# Parallel_Interfaces.net
KiCad netlist of a schematic drawn in Altium Designer
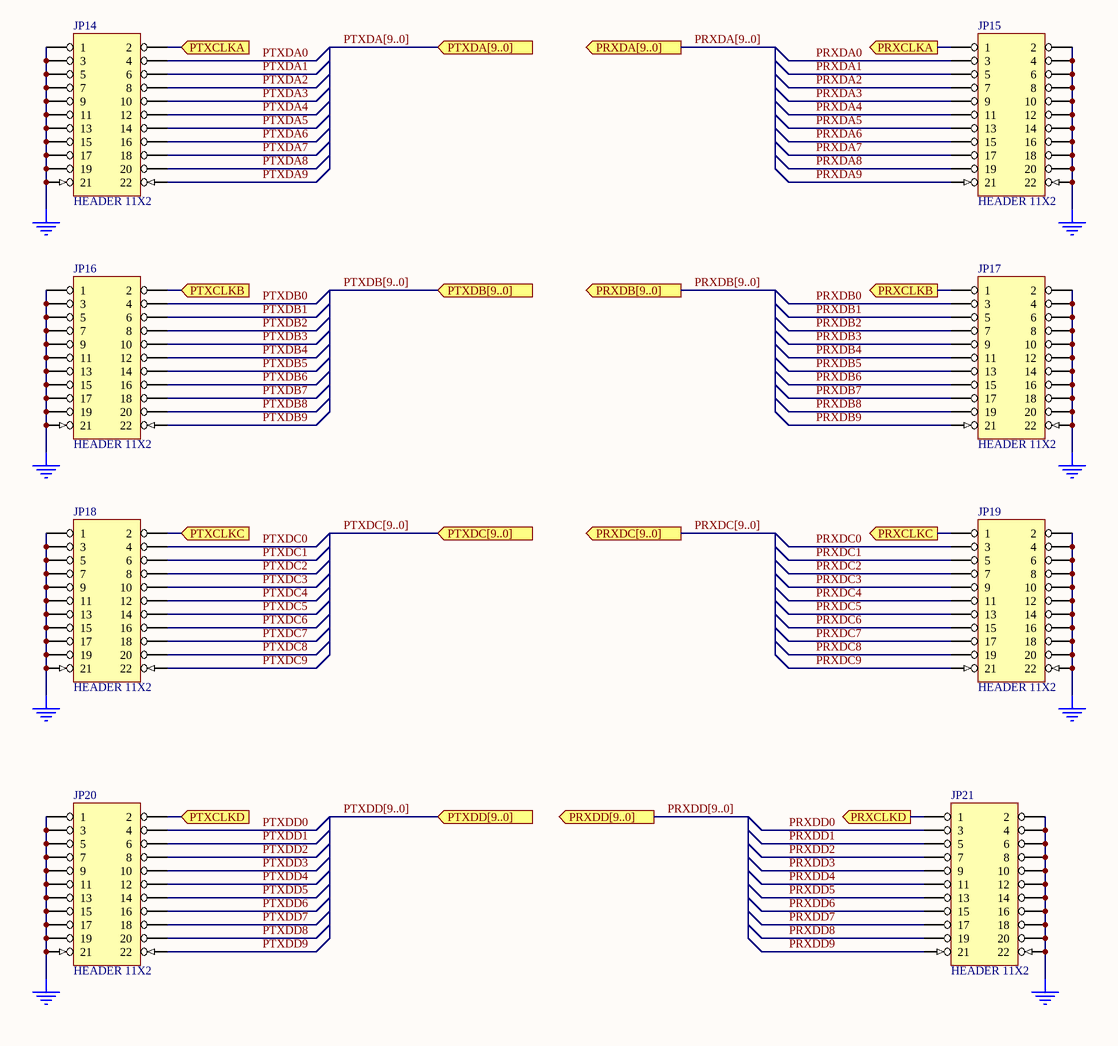
[diagram p0: Parallel Interfaces.SchDoc]

(export (version "E")
  (design (tool "Eeschema 10.0.6"))
  (components
    (comp (ref "JP14")
      (value "~")
      (footprint "2X11PIN")
      (libsource (lib "Cypress Molson") (part "HEADER 11X2"))
    )
    (comp (ref "JP15")
      (value "~")
      (footprint "2X11PIN")
      (libsource (lib "Cypress Molson") (part "HEADER 11X2"))
    )
    (comp (ref "JP16")
      (value "~")
      (footprint "2X11PIN")
      (libsource (lib "Cypress Molson") (part "HEADER 11X2"))
    )
    (comp (ref "JP17")
      (value "~")
      (footprint "2X11PIN")
      (libsource (lib "Cypress Molson") (part "HEADER 11X2"))
    )
    (comp (ref "JP18")
      (value "~")
      (footprint "2X11PIN")
      (libsource (lib "Cypress Molson") (part "HEADER 11X2"))
    )
    (comp (ref "JP19")
      (value "~")
      (footprint "2X11PIN")
      (libsource (lib "Cypress Molson") (part "HEADER 11X2"))
    )
    (comp (ref "JP20")
      (value "~")
      (footprint "2X11PIN")
      (libsource (lib "Cypress Molson") (part "HEADER 11X2"))
    )
    (comp (ref "JP21")
      (value "~")
      (footprint "2X11PIN")
      (libsource (lib "Cypress Molson") (part "HEADER 11X2"))
    )
  )
  (nets
    (net (code "1") (name "/PRXCLKA") (class "Default")
      (node (ref "JP15") (pin "1") (pinfunction "1_1") (pintype "passive"))
    )
    (net (code "2") (name "/PRXCLKB") (class "Default")
      (node (ref "JP17") (pin "1") (pinfunction "1_1") (pintype "passive"))
    )
    (net (code "3") (name "/PRXCLKC") (class "Default")
      (node (ref "JP19") (pin "1") (pinfunction "1_1") (pintype "passive"))
    )
    (net (code "4") (name "/PRXCLKD") (class "Default")
      (node (ref "JP21") (pin "1") (pinfunction "1_1") (pintype "passive"))
    )
    (net (code "5") (name "/PRXDA0") (class "Default")
      (node (ref "JP15") (pin "3") (pinfunction "3_3") (pintype "passive"))
    )
    (net (code "6") (name "/PRXDA1") (class "Default")
      (node (ref "JP15") (pin "5") (pinfunction "5_5") (pintype "passive"))
    )
    (net (code "7") (name "/PRXDA2") (class "Default")
      (node (ref "JP15") (pin "7") (pinfunction "7_7") (pintype "passive"))
    )
    (net (code "8") (name "/PRXDA3") (class "Default")
      (node (ref "JP15") (pin "9") (pinfunction "9_9") (pintype "passive"))
    )
    (net (code "9") (name "/PRXDA4") (class "Default")
      (node (ref "JP15") (pin "11") (pinfunction "11_11") (pintype "passive"))
    )
    (net (code "10") (name "/PRXDA5") (class "Default")
      (node (ref "JP15") (pin "13") (pinfunction "13_13") (pintype "passive"))
    )
    (net (code "11") (name "/PRXDA6") (class "Default")
      (node (ref "JP15") (pin "15") (pinfunction "15_15") (pintype "passive"))
    )
    (net (code "12") (name "/PRXDA7") (class "Default")
      (node (ref "JP15") (pin "17") (pinfunction "17_17") (pintype "passive"))
    )
    (net (code "13") (name "/PRXDA8") (class "Default")
      (node (ref "JP15") (pin "19") (pinfunction "19_19") (pintype "passive"))
    )
    (net (code "14") (name "/PRXDA9") (class "Default")
      (node (ref "JP15") (pin "21") (pinfunction "21_21") (pintype "input"))
    )
    (net (code "16") (name "/PRXDB0") (class "Default")
      (node (ref "JP17") (pin "3") (pinfunction "3_3") (pintype "passive"))
    )
    (net (code "17") (name "/PRXDB1") (class "Default")
      (node (ref "JP17") (pin "5") (pinfunction "5_5") (pintype "passive"))
    )
    (net (code "18") (name "/PRXDB2") (class "Default")
      (node (ref "JP17") (pin "7") (pinfunction "7_7") (pintype "passive"))
    )
    (net (code "19") (name "/PRXDB3") (class "Default")
      (node (ref "JP17") (pin "9") (pinfunction "9_9") (pintype "passive"))
    )
    (net (code "20") (name "/PRXDB4") (class "Default")
      (node (ref "JP17") (pin "11") (pinfunction "11_11") (pintype "passive"))
    )
    (net (code "21") (name "/PRXDB5") (class "Default")
      (node (ref "JP17") (pin "13") (pinfunction "13_13") (pintype "passive"))
    )
    (net (code "22") (name "/PRXDB6") (class "Default")
      (node (ref "JP17") (pin "15") (pinfunction "15_15") (pintype "passive"))
    )
    (net (code "23") (name "/PRXDB7") (class "Default")
      (node (ref "JP17") (pin "17") (pinfunction "17_17") (pintype "passive"))
    )
    (net (code "24") (name "/PRXDB8") (class "Default")
      (node (ref "JP17") (pin "19") (pinfunction "19_19") (pintype "passive"))
    )
    (net (code "25") (name "/PRXDB9") (class "Default")
      (node (ref "JP17") (pin "21") (pinfunction "21_21") (pintype "input"))
    )
    (net (code "27") (name "/PRXDC0") (class "Default")
      (node (ref "JP19") (pin "3") (pinfunction "3_3") (pintype "passive"))
    )
    (net (code "28") (name "/PRXDC1") (class "Default")
      (node (ref "JP19") (pin "5") (pinfunction "5_5") (pintype "passive"))
    )
    (net (code "29") (name "/PRXDC2") (class "Default")
      (node (ref "JP19") (pin "7") (pinfunction "7_7") (pintype "passive"))
    )
    (net (code "30") (name "/PRXDC3") (class "Default")
      (node (ref "JP19") (pin "9") (pinfunction "9_9") (pintype "passive"))
    )
    (net (code "31") (name "/PRXDC4") (class "Default")
      (node (ref "JP19") (pin "11") (pinfunction "11_11") (pintype "passive"))
    )
    (net (code "32") (name "/PRXDC5") (class "Default")
      (node (ref "JP19") (pin "13") (pinfunction "13_13") (pintype "passive"))
    )
    (net (code "33") (name "/PRXDC6") (class "Default")
      (node (ref "JP19") (pin "15") (pinfunction "15_15") (pintype "passive"))
    )
    (net (code "34") (name "/PRXDC7") (class "Default")
      (node (ref "JP19") (pin "17") (pinfunction "17_17") (pintype "passive"))
    )
    (net (code "35") (name "/PRXDC8") (class "Default")
      (node (ref "JP19") (pin "19") (pinfunction "19_19") (pintype "passive"))
    )
    (net (code "36") (name "/PRXDC9") (class "Default")
      (node (ref "JP19") (pin "21") (pinfunction "21_21") (pintype "input"))
    )
    (net (code "38") (name "/PRXDD0") (class "Default")
      (node (ref "JP21") (pin "3") (pinfunction "3_3") (pintype "passive"))
    )
    (net (code "39") (name "/PRXDD1") (class "Default")
      (node (ref "JP21") (pin "5") (pinfunction "5_5") (pintype "passive"))
    )
    (net (code "40") (name "/PRXDD2") (class "Default")
      (node (ref "JP21") (pin "7") (pinfunction "7_7") (pintype "passive"))
    )
    (net (code "41") (name "/PRXDD3") (class "Default")
      (node (ref "JP21") (pin "9") (pinfunction "9_9") (pintype "passive"))
    )
    (net (code "42") (name "/PRXDD4") (class "Default")
      (node (ref "JP21") (pin "11") (pinfunction "11_11") (pintype "passive"))
    )
    (net (code "43") (name "/PRXDD5") (class "Default")
      (node (ref "JP21") (pin "13") (pinfunction "13_13") (pintype "passive"))
    )
    (net (code "44") (name "/PRXDD6") (class "Default")
      (node (ref "JP21") (pin "15") (pinfunction "15_15") (pintype "passive"))
    )
    (net (code "45") (name "/PRXDD7") (class "Default")
      (node (ref "JP21") (pin "17") (pinfunction "17_17") (pintype "passive"))
    )
    (net (code "46") (name "/PRXDD8") (class "Default")
      (node (ref "JP21") (pin "19") (pinfunction "19_19") (pintype "passive"))
    )
    (net (code "47") (name "/PRXDD9") (class "Default")
      (node (ref "JP21") (pin "21") (pinfunction "21_21") (pintype "input"))
    )
    (net (code "49") (name "/PTXCLKA") (class "Default")
      (node (ref "JP14") (pin "2") (pinfunction "2_2") (pintype "passive"))
    )
    (net (code "50") (name "/PTXCLKB") (class "Default")
      (node (ref "JP16") (pin "2") (pinfunction "2_2") (pintype "passive"))
    )
    (net (code "51") (name "/PTXCLKC") (class "Default")
      (node (ref "JP18") (pin "2") (pinfunction "2_2") (pintype "passive"))
    )
    (net (code "52") (name "/PTXCLKD") (class "Default")
      (node (ref "JP20") (pin "2") (pinfunction "2_2") (pintype "passive"))
    )
    (net (code "53") (name "/PTXDA0") (class "Default")
      (node (ref "JP14") (pin "4") (pinfunction "4_4") (pintype "passive"))
    )
    (net (code "54") (name "/PTXDA1") (class "Default")
      (node (ref "JP14") (pin "6") (pinfunction "6_6") (pintype "passive"))
    )
    (net (code "55") (name "/PTXDA2") (class "Default")
      (node (ref "JP14") (pin "8") (pinfunction "8_8") (pintype "passive"))
    )
    (net (code "56") (name "/PTXDA3") (class "Default")
      (node (ref "JP14") (pin "10") (pinfunction "10_10") (pintype "passive"))
    )
    (net (code "57") (name "/PTXDA4") (class "Default")
      (node (ref "JP14") (pin "12") (pinfunction "12_12") (pintype "passive"))
    )
    (net (code "58") (name "/PTXDA5") (class "Default")
      (node (ref "JP14") (pin "14") (pinfunction "14_14") (pintype "passive"))
    )
    (net (code "59") (name "/PTXDA6") (class "Default")
      (node (ref "JP14") (pin "16") (pinfunction "16_16") (pintype "passive"))
    )
    (net (code "60") (name "/PTXDA7") (class "Default")
      (node (ref "JP14") (pin "18") (pinfunction "18_18") (pintype "passive"))
    )
    (net (code "61") (name "/PTXDA8") (class "Default")
      (node (ref "JP14") (pin "20") (pinfunction "20_20") (pintype "passive"))
    )
    (net (code "62") (name "/PTXDA9") (class "Default")
      (node (ref "JP14") (pin "22") (pinfunction "22_22") (pintype "input"))
    )
    (net (code "64") (name "/PTXDB0") (class "Default")
      (node (ref "JP16") (pin "4") (pinfunction "4_4") (pintype "passive"))
    )
    (net (code "65") (name "/PTXDB1") (class "Default")
      (node (ref "JP16") (pin "6") (pinfunction "6_6") (pintype "passive"))
    )
    (net (code "66") (name "/PTXDB2") (class "Default")
      (node (ref "JP16") (pin "8") (pinfunction "8_8") (pintype "passive"))
    )
    (net (code "67") (name "/PTXDB3") (class "Default")
      (node (ref "JP16") (pin "10") (pinfunction "10_10") (pintype "passive"))
    )
    (net (code "68") (name "/PTXDB4") (class "Default")
      (node (ref "JP16") (pin "12") (pinfunction "12_12") (pintype "passive"))
    )
    (net (code "69") (name "/PTXDB5") (class "Default")
      (node (ref "JP16") (pin "14") (pinfunction "14_14") (pintype "passive"))
    )
    (net (code "70") (name "/PTXDB6") (class "Default")
      (node (ref "JP16") (pin "16") (pinfunction "16_16") (pintype "passive"))
    )
    (net (code "71") (name "/PTXDB7") (class "Default")
      (node (ref "JP16") (pin "18") (pinfunction "18_18") (pintype "passive"))
    )
    (net (code "72") (name "/PTXDB8") (class "Default")
      (node (ref "JP16") (pin "20") (pinfunction "20_20") (pintype "passive"))
    )
    (net (code "73") (name "/PTXDB9") (class "Default")
      (node (ref "JP16") (pin "22") (pinfunction "22_22") (pintype "input"))
    )
    (net (code "75") (name "/PTXDC0") (class "Default")
      (node (ref "JP18") (pin "4") (pinfunction "4_4") (pintype "passive"))
    )
    (net (code "76") (name "/PTXDC1") (class "Default")
      (node (ref "JP18") (pin "6") (pinfunction "6_6") (pintype "passive"))
    )
    (net (code "77") (name "/PTXDC2") (class "Default")
      (node (ref "JP18") (pin "8") (pinfunction "8_8") (pintype "passive"))
    )
    (net (code "78") (name "/PTXDC3") (class "Default")
      (node (ref "JP18") (pin "10") (pinfunction "10_10") (pintype "passive"))
    )
    (net (code "79") (name "/PTXDC4") (class "Default")
      (node (ref "JP18") (pin "12") (pinfunction "12_12") (pintype "passive"))
    )
    (net (code "80") (name "/PTXDC5") (class "Default")
      (node (ref "JP18") (pin "14") (pinfunction "14_14") (pintype "passive"))
    )
    (net (code "81") (name "/PTXDC6") (class "Default")
      (node (ref "JP18") (pin "16") (pinfunction "16_16") (pintype "passive"))
    )
    (net (code "82") (name "/PTXDC7") (class "Default")
      (node (ref "JP18") (pin "18") (pinfunction "18_18") (pintype "passive"))
    )
    (net (code "83") (name "/PTXDC8") (class "Default")
      (node (ref "JP18") (pin "20") (pinfunction "20_20") (pintype "passive"))
    )
    (net (code "84") (name "/PTXDC9") (class "Default")
      (node (ref "JP18") (pin "22") (pinfunction "22_22") (pintype "input"))
    )
    (net (code "86") (name "/PTXDD0") (class "Default")
      (node (ref "JP20") (pin "4") (pinfunction "4_4") (pintype "passive"))
    )
    (net (code "87") (name "/PTXDD1") (class "Default")
      (node (ref "JP20") (pin "6") (pinfunction "6_6") (pintype "passive"))
    )
    (net (code "88") (name "/PTXDD2") (class "Default")
      (node (ref "JP20") (pin "8") (pinfunction "8_8") (pintype "passive"))
    )
    (net (code "89") (name "/PTXDD3") (class "Default")
      (node (ref "JP20") (pin "10") (pinfunction "10_10") (pintype "passive"))
    )
    (net (code "90") (name "/PTXDD4") (class "Default")
      (node (ref "JP20") (pin "12") (pinfunction "12_12") (pintype "passive"))
    )
    (net (code "91") (name "/PTXDD5") (class "Default")
      (node (ref "JP20") (pin "14") (pinfunction "14_14") (pintype "passive"))
    )
    (net (code "92") (name "/PTXDD6") (class "Default")
      (node (ref "JP20") (pin "16") (pinfunction "16_16") (pintype "passive"))
    )
    (net (code "93") (name "/PTXDD7") (class "Default")
      (node (ref "JP20") (pin "18") (pinfunction "18_18") (pintype "passive"))
    )
    (net (code "94") (name "/PTXDD8") (class "Default")
      (node (ref "JP20") (pin "20") (pinfunction "20_20") (pintype "passive"))
    )
    (net (code "95") (name "/PTXDD9") (class "Default")
      (node (ref "JP20") (pin "22") (pinfunction "22_22") (pintype "input"))
    )
    (net (code "97") (name "GND") (class "Default")
      (node (ref "JP14") (pin "1") (pinfunction "1_1") (pintype "passive"))
      (node (ref "JP14") (pin "11") (pinfunction "11_11") (pintype "passive"))
      (node (ref "JP14") (pin "13") (pinfunction "13_13") (pintype "passive"))
      (node (ref "JP14") (pin "15") (pinfunction "15_15") (pintype "passive"))
      (node (ref "JP14") (pin "17") (pinfunction "17_17") (pintype "passive"))
      (node (ref "JP14") (pin "19") (pinfunction "19_19") (pintype "passive"))
      (node (ref "JP14") (pin "21") (pinfunction "21_21") (pintype "input"))
      (node (ref "JP14") (pin "3") (pinfunction "3_3") (pintype "passive"))
      (node (ref "JP14") (pin "5") (pinfunction "5_5") (pintype "passive"))
      (node (ref "JP14") (pin "7") (pinfunction "7_7") (pintype "passive"))
      (node (ref "JP14") (pin "9") (pinfunction "9_9") (pintype "passive"))
      (node (ref "JP15") (pin "10") (pinfunction "10_10") (pintype "passive"))
      (node (ref "JP15") (pin "12") (pinfunction "12_12") (pintype "passive"))
      (node (ref "JP15") (pin "14") (pinfunction "14_14") (pintype "passive"))
      (node (ref "JP15") (pin "16") (pinfunction "16_16") (pintype "passive"))
      (node (ref "JP15") (pin "18") (pinfunction "18_18") (pintype "passive"))
      (node (ref "JP15") (pin "2") (pinfunction "2_2") (pintype "passive"))
      (node (ref "JP15") (pin "20") (pinfunction "20_20") (pintype "passive"))
      (node (ref "JP15") (pin "22") (pinfunction "22_22") (pintype "input"))
      (node (ref "JP15") (pin "4") (pinfunction "4_4") (pintype "passive"))
      (node (ref "JP15") (pin "6") (pinfunction "6_6") (pintype "passive"))
      (node (ref "JP15") (pin "8") (pinfunction "8_8") (pintype "passive"))
      (node (ref "JP16") (pin "1") (pinfunction "1_1") (pintype "passive"))
      (node (ref "JP16") (pin "11") (pinfunction "11_11") (pintype "passive"))
      (node (ref "JP16") (pin "13") (pinfunction "13_13") (pintype "passive"))
      (node (ref "JP16") (pin "15") (pinfunction "15_15") (pintype "passive"))
      (node (ref "JP16") (pin "17") (pinfunction "17_17") (pintype "passive"))
      (node (ref "JP16") (pin "19") (pinfunction "19_19") (pintype "passive"))
      (node (ref "JP16") (pin "21") (pinfunction "21_21") (pintype "input"))
      (node (ref "JP16") (pin "3") (pinfunction "3_3") (pintype "passive"))
      (node (ref "JP16") (pin "5") (pinfunction "5_5") (pintype "passive"))
      (node (ref "JP16") (pin "7") (pinfunction "7_7") (pintype "passive"))
      (node (ref "JP16") (pin "9") (pinfunction "9_9") (pintype "passive"))
      (node (ref "JP17") (pin "10") (pinfunction "10_10") (pintype "passive"))
      (node (ref "JP17") (pin "12") (pinfunction "12_12") (pintype "passive"))
      (node (ref "JP17") (pin "14") (pinfunction "14_14") (pintype "passive"))
      (node (ref "JP17") (pin "16") (pinfunction "16_16") (pintype "passive"))
      (node (ref "JP17") (pin "18") (pinfunction "18_18") (pintype "passive"))
      (node (ref "JP17") (pin "2") (pinfunction "2_2") (pintype "passive"))
      (node (ref "JP17") (pin "20") (pinfunction "20_20") (pintype "passive"))
      (node (ref "JP17") (pin "22") (pinfunction "22_22") (pintype "input"))
      (node (ref "JP17") (pin "4") (pinfunction "4_4") (pintype "passive"))
      (node (ref "JP17") (pin "6") (pinfunction "6_6") (pintype "passive"))
      (node (ref "JP17") (pin "8") (pinfunction "8_8") (pintype "passive"))
      (node (ref "JP18") (pin "1") (pinfunction "1_1") (pintype "passive"))
      (node (ref "JP18") (pin "11") (pinfunction "11_11") (pintype "passive"))
      (node (ref "JP18") (pin "13") (pinfunction "13_13") (pintype "passive"))
      (node (ref "JP18") (pin "15") (pinfunction "15_15") (pintype "passive"))
      (node (ref "JP18") (pin "17") (pinfunction "17_17") (pintype "passive"))
      (node (ref "JP18") (pin "19") (pinfunction "19_19") (pintype "passive"))
      (node (ref "JP18") (pin "21") (pinfunction "21_21") (pintype "input"))
      (node (ref "JP18") (pin "3") (pinfunction "3_3") (pintype "passive"))
      (node (ref "JP18") (pin "5") (pinfunction "5_5") (pintype "passive"))
      (node (ref "JP18") (pin "7") (pinfunction "7_7") (pintype "passive"))
      (node (ref "JP18") (pin "9") (pinfunction "9_9") (pintype "passive"))
      (node (ref "JP19") (pin "10") (pinfunction "10_10") (pintype "passive"))
      (node (ref "JP19") (pin "12") (pinfunction "12_12") (pintype "passive"))
      (node (ref "JP19") (pin "14") (pinfunction "14_14") (pintype "passive"))
      (node (ref "JP19") (pin "16") (pinfunction "16_16") (pintype "passive"))
      (node (ref "JP19") (pin "18") (pinfunction "18_18") (pintype "passive"))
      (node (ref "JP19") (pin "2") (pinfunction "2_2") (pintype "passive"))
      (node (ref "JP19") (pin "20") (pinfunction "20_20") (pintype "passive"))
      (node (ref "JP19") (pin "22") (pinfunction "22_22") (pintype "input"))
      (node (ref "JP19") (pin "4") (pinfunction "4_4") (pintype "passive"))
      (node (ref "JP19") (pin "6") (pinfunction "6_6") (pintype "passive"))
      (node (ref "JP19") (pin "8") (pinfunction "8_8") (pintype "passive"))
      (node (ref "JP20") (pin "1") (pinfunction "1_1") (pintype "passive"))
      (node (ref "JP20") (pin "11") (pinfunction "11_11") (pintype "passive"))
      (node (ref "JP20") (pin "13") (pinfunction "13_13") (pintype "passive"))
      (node (ref "JP20") (pin "15") (pinfunction "15_15") (pintype "passive"))
      (node (ref "JP20") (pin "17") (pinfunction "17_17") (pintype "passive"))
      (node (ref "JP20") (pin "19") (pinfunction "19_19") (pintype "passive"))
      (node (ref "JP20") (pin "21") (pinfunction "21_21") (pintype "input"))
      (node (ref "JP20") (pin "3") (pinfunction "3_3") (pintype "passive"))
      (node (ref "JP20") (pin "5") (pinfunction "5_5") (pintype "passive"))
      (node (ref "JP20") (pin "7") (pinfunction "7_7") (pintype "passive"))
      (node (ref "JP20") (pin "9") (pinfunction "9_9") (pintype "passive"))
      (node (ref "JP21") (pin "10") (pinfunction "10_10") (pintype "passive"))
      (node (ref "JP21") (pin "12") (pinfunction "12_12") (pintype "passive"))
      (node (ref "JP21") (pin "14") (pinfunction "14_14") (pintype "passive"))
      (node (ref "JP21") (pin "16") (pinfunction "16_16") (pintype "passive"))
      (node (ref "JP21") (pin "18") (pinfunction "18_18") (pintype "passive"))
      (node (ref "JP21") (pin "2") (pinfunction "2_2") (pintype "passive"))
      (node (ref "JP21") (pin "20") (pinfunction "20_20") (pintype "passive"))
      (node (ref "JP21") (pin "22") (pinfunction "22_22") (pintype "input"))
      (node (ref "JP21") (pin "4") (pinfunction "4_4") (pintype "passive"))
      (node (ref "JP21") (pin "6") (pinfunction "6_6") (pintype "passive"))
      (node (ref "JP21") (pin "8") (pinfunction "8_8") (pintype "passive"))
    )
  )
)
